# Camera_LED_Display.net
KiCad netlist of a schematic drawn in Altium Designer
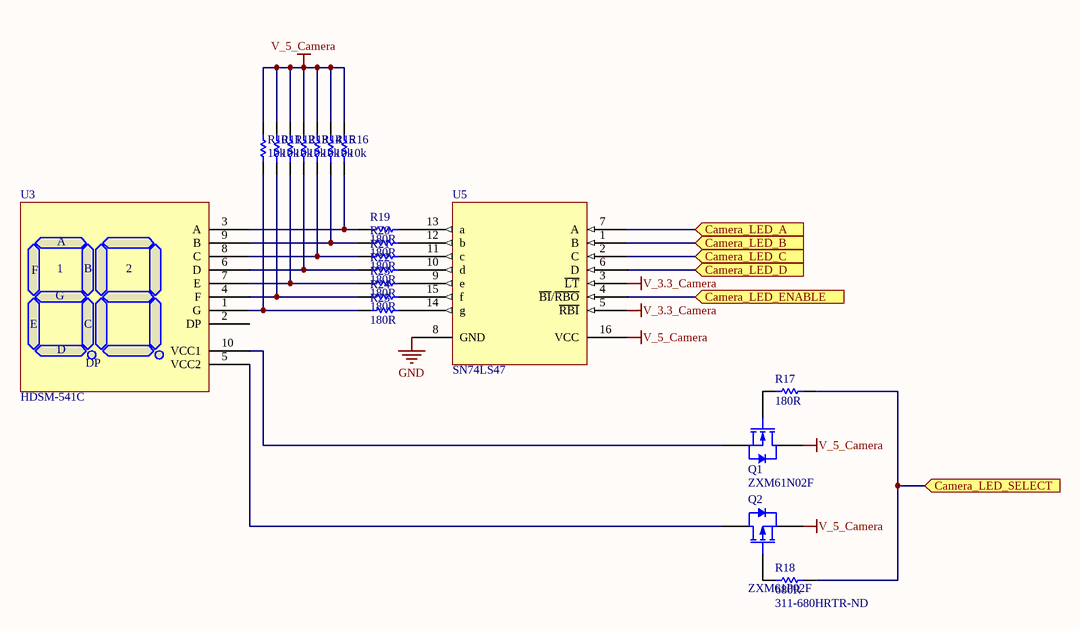
[diagram p0: Camera_LED_Display.SchDoc]

(export (version "E")
  (design (tool "Eeschema 10.0.6"))
  (components
    (comp (ref "Q1")
      (value "ZXM61N02F")
      (footprint "SOT-23")
      (description "20V N-channel enhancement mode MOSFET")
      (fields (field (name "MANUFACTURER") "Zetex") (field (name "PART NUMBER") "TF_ZXM61N02F"))
      (libsource (lib "ENEL429_4") (part "TF_ZXM61N02F"))
    )
    (comp (ref "Q2")
      (value "ZXM61P02F")
      (footprint "SOT23")
      (description "20V P-channel enhancement mode MOSFET")
      (fields (field (name "MANUFACTURER") "Zetex") (field (name "PART NUMBER") "TF_ZXM61P02F"))
      (libsource (lib "ENEL429_4") (part "TF_ZXM61P02F"))
    )
    (comp (ref "R10")
      (value "10k")
      (footprint "0603")
      (description "RES 10.0K OHM 1/10W 1% 0603 SMD")
      (fields (field (name "MANUFACTURER") "Yageo") (field (name "PART NUMBER") "RS_10k 0603"))
      (libsource (lib "ENEL429_4") (part "RS_10k 0603"))
    )
    (comp (ref "R11")
      (value "10k")
      (footprint "0603")
      (description "RES 10.0K OHM 1/10W 1% 0603 SMD")
      (fields (field (name "MANUFACTURER") "Yageo") (field (name "PART NUMBER") "RS_10k 0603"))
      (libsource (lib "ENEL429_4") (part "RS_10k 0603"))
    )
    (comp (ref "R12")
      (value "10k")
      (footprint "0603")
      (description "RES 10.0K OHM 1/10W 1% 0603 SMD")
      (fields (field (name "MANUFACTURER") "Yageo") (field (name "PART NUMBER") "RS_10k 0603"))
      (libsource (lib "ENEL429_4") (part "RS_10k 0603"))
    )
    (comp (ref "R13")
      (value "10k")
      (footprint "0603")
      (description "RES 10.0K OHM 1/10W 1% 0603 SMD")
      (fields (field (name "MANUFACTURER") "Yageo") (field (name "PART NUMBER") "RS_10k 0603"))
      (libsource (lib "ENEL429_4") (part "RS_10k 0603"))
    )
    (comp (ref "R14")
      (value "10k")
      (footprint "0603")
      (description "RES 10.0K OHM 1/10W 1% 0603 SMD")
      (fields (field (name "MANUFACTURER") "Yageo") (field (name "PART NUMBER") "RS_10k 0603"))
      (libsource (lib "ENEL429_4") (part "RS_10k 0603"))
    )
    (comp (ref "R15")
      (value "10k")
      (footprint "0603")
      (description "RES 10.0K OHM 1/10W 1% 0603 SMD")
      (fields (field (name "MANUFACTURER") "Yageo") (field (name "PART NUMBER") "RS_10k 0603"))
      (libsource (lib "ENEL429_4") (part "RS_10k 0603"))
    )
    (comp (ref "R16")
      (value "10k")
      (footprint "0603")
      (description "RES 10.0K OHM 1/10W 1% 0603 SMD")
      (fields (field (name "MANUFACTURER") "Yageo") (field (name "PART NUMBER") "RS_10k 0603"))
      (libsource (lib "ENEL429_4") (part "RS_10k 0603"))
    )
    (comp (ref "R17")
      (value "180R")
      (footprint "0603")
      (description "RES 180OHM 1/10W 1% 0603 SMD")
      (fields (field (name "MANUFACTURER") "Panasonic - ECG") (field (name "PART NUMBER") "RS_180R 0603"))
      (libsource (lib "ENEL429_4") (part "RS_180R 0603"))
    )
    (comp (ref "R18")
      (value "680R")
      (footprint "0603")
      (description "RES 680 OHM 1/10W 1% 0603 SMD")
      (fields
        (field (name "MANUFACTURER") "Yageo")
        (field (name "SUPPLIER PART NUMBER 1") "311-680HRTR-ND")
        (field (name "PART NUMBER") "RS_680R 0603")
      )
      (libsource (lib "ENEL429_4") (part "RS_680R 0603"))
    )
    (comp (ref "R19")
      (value "180R")
      (footprint "0603")
      (description "RES 180OHM 1/10W 1% 0603 SMD")
      (fields (field (name "MANUFACTURER") "Panasonic - ECG") (field (name "PART NUMBER") "RS_180R 0603"))
      (libsource (lib "ENEL429_4") (part "RS_180R 0603"))
    )
    (comp (ref "R20")
      (value "180R")
      (footprint "0603")
      (description "RES 180OHM 1/10W 1% 0603 SMD")
      (fields (field (name "MANUFACTURER") "Panasonic - ECG") (field (name "PART NUMBER") "RS_180R 0603"))
      (libsource (lib "ENEL429_4") (part "RS_180R 0603"))
    )
    (comp (ref "R21")
      (value "180R")
      (footprint "0603")
      (description "RES 180OHM 1/10W 1% 0603 SMD")
      (fields (field (name "MANUFACTURER") "Panasonic - ECG") (field (name "PART NUMBER") "RS_180R 0603"))
      (libsource (lib "ENEL429_4") (part "RS_180R 0603"))
    )
    (comp (ref "R22")
      (value "180R")
      (footprint "0603")
      (description "RES 180OHM 1/10W 1% 0603 SMD")
      (fields (field (name "MANUFACTURER") "Panasonic - ECG") (field (name "PART NUMBER") "RS_180R 0603"))
      (libsource (lib "ENEL429_4") (part "RS_180R 0603"))
    )
    (comp (ref "R23")
      (value "180R")
      (footprint "0603")
      (description "RES 180OHM 1/10W 1% 0603 SMD")
      (fields (field (name "MANUFACTURER") "Panasonic - ECG") (field (name "PART NUMBER") "RS_180R 0603"))
      (libsource (lib "ENEL429_4") (part "RS_180R 0603"))
    )
    (comp (ref "R24")
      (value "180R")
      (footprint "0603")
      (description "RES 180OHM 1/10W 1% 0603 SMD")
      (fields (field (name "MANUFACTURER") "Panasonic - ECG") (field (name "PART NUMBER") "RS_180R 0603"))
      (libsource (lib "ENEL429_4") (part "RS_180R 0603"))
    )
    (comp (ref "R25")
      (value "180R")
      (footprint "0603")
      (description "RES 180OHM 1/10W 1% 0603 SMD")
      (fields (field (name "MANUFACTURER") "Panasonic - ECG") (field (name "PART NUMBER") "RS_180R 0603"))
      (libsource (lib "ENEL429_4") (part "RS_180R 0603"))
    )
    (comp (ref "U3")
      (value "HDSM-541C")
      (footprint "HDSM-541C")
      (description "2 character 7 segment display")
      (fields (field (name "MANUFACTURER") "AVAGO TECHNOLOGIES"))
      (libsource (lib "Wacky_1") (part "HDSM-541C"))
    )
    (comp (ref "U5")
      (value "SN74LS47")
      (footprint "SOP127P780X200-16N")
      (fields (field (name "MANUFACTURER") "Texas Instruments"))
      (libsource (lib "Wacky_1") (part "SN74LS47"))
    )
  )
  (nets
    (net (code "1") (name "/Camera_LED_A") (class "Default")
      (node (ref "U5") (pin "7") (pinfunction "A_7") (pintype "input"))
    )
    (net (code "2") (name "/Camera_LED_B") (class "Default")
      (node (ref "U5") (pin "1") (pinfunction "B_1") (pintype "input"))
    )
    (net (code "3") (name "/Camera_LED_C") (class "Default")
      (node (ref "U5") (pin "2") (pinfunction "C_2") (pintype "input"))
    )
    (net (code "4") (name "/Camera_LED_D") (class "Default")
      (node (ref "U5") (pin "6") (pinfunction "D_6") (pintype "input"))
    )
    (net (code "5") (name "/Camera_LED_ENABLE") (class "Default")
      (node (ref "U5") (pin "4") (pinfunction "~{BI}/~{RBO}_4") (pintype "input"))
    )
    (net (code "6") (name "/Camera_LED_SELECT") (class "Default")
      (node (ref "R17") (pin "2") (pinfunction "2_2") (pintype "passive"))
      (node (ref "R18") (pin "2") (pinfunction "2_2") (pintype "passive"))
    )
    (net (code "7") (name "GND") (class "Default")
      (node (ref "U5") (pin "8") (pinfunction "GND_8") (pintype "passive"))
    )
    (net (code "8") (name "Net-(Q1-G)") (class "Default")
      (node (ref "Q1") (pin "1") (pinfunction "G_1") (pintype "passive"))
      (node (ref "R17") (pin "1") (pinfunction "1_1") (pintype "passive"))
    )
    (net (code "9") (name "Net-(Q1-S)") (class "Default")
      (node (ref "Q1") (pin "2") (pinfunction "S_2") (pintype "passive"))
      (node (ref "U3") (pin "10") (pinfunction "VCC1_10") (pintype "passive"))
    )
    (net (code "10") (name "Net-(Q2-D)") (class "Default")
      (node (ref "Q2") (pin "3") (pinfunction "D_3") (pintype "passive"))
      (node (ref "U3") (pin "5") (pinfunction "VCC2_5") (pintype "passive"))
    )
    (net (code "11") (name "Net-(Q2-G)") (class "Default")
      (node (ref "Q2") (pin "1") (pinfunction "G_1") (pintype "passive"))
      (node (ref "R18") (pin "1") (pinfunction "1_1") (pintype "passive"))
    )
    (net (code "12") (name "Net-(U3-A)") (class "Default")
      (node (ref "R16") (pin "1") (pinfunction "1_1") (pintype "passive"))
      (node (ref "R19") (pin "1") (pinfunction "1_1") (pintype "passive"))
      (node (ref "U3") (pin "3") (pinfunction "A_3") (pintype "passive"))
    )
    (net (code "13") (name "Net-(U3-B)") (class "Default")
      (node (ref "R15") (pin "1") (pinfunction "1_1") (pintype "passive"))
      (node (ref "R20") (pin "1") (pinfunction "1_1") (pintype "passive"))
      (node (ref "U3") (pin "9") (pinfunction "B_9") (pintype "passive"))
    )
    (net (code "14") (name "Net-(U3-C)") (class "Default")
      (node (ref "R14") (pin "1") (pinfunction "1_1") (pintype "passive"))
      (node (ref "R21") (pin "1") (pinfunction "1_1") (pintype "passive"))
      (node (ref "U3") (pin "8") (pinfunction "C_8") (pintype "passive"))
    )
    (net (code "15") (name "Net-(U3-D)") (class "Default")
      (node (ref "R13") (pin "1") (pinfunction "1_1") (pintype "passive"))
      (node (ref "R22") (pin "1") (pinfunction "1_1") (pintype "passive"))
      (node (ref "U3") (pin "6") (pinfunction "D_6") (pintype "passive"))
    )
    (net (code "16") (name "Net-(U3-E)") (class "Default")
      (node (ref "R12") (pin "1") (pinfunction "1_1") (pintype "passive"))
      (node (ref "R23") (pin "1") (pinfunction "1_1") (pintype "passive"))
      (node (ref "U3") (pin "7") (pinfunction "E_7") (pintype "passive"))
    )
    (net (code "17") (name "Net-(U3-F)") (class "Default")
      (node (ref "R11") (pin "1") (pinfunction "1_1") (pintype "passive"))
      (node (ref "R24") (pin "1") (pinfunction "1_1") (pintype "passive"))
      (node (ref "U3") (pin "4") (pinfunction "F_4") (pintype "passive"))
    )
    (net (code "18") (name "Net-(U3-G)") (class "Default")
      (node (ref "R10") (pin "1") (pinfunction "1_1") (pintype "passive"))
      (node (ref "R25") (pin "1") (pinfunction "1_1") (pintype "passive"))
      (node (ref "U3") (pin "1") (pinfunction "G_1") (pintype "passive"))
    )
    (net (code "19") (name "Net-(U5-a)") (class "Default")
      (node (ref "R19") (pin "2") (pinfunction "2_2") (pintype "passive"))
      (node (ref "U5") (pin "13") (pinfunction "a_13") (pintype "output"))
    )
    (net (code "20") (name "Net-(U5-b)") (class "Default")
      (node (ref "R20") (pin "2") (pinfunction "2_2") (pintype "passive"))
      (node (ref "U5") (pin "12") (pinfunction "b_12") (pintype "output"))
    )
    (net (code "21") (name "Net-(U5-c)") (class "Default")
      (node (ref "R21") (pin "2") (pinfunction "2_2") (pintype "passive"))
      (node (ref "U5") (pin "11") (pinfunction "c_11") (pintype "output"))
    )
    (net (code "22") (name "Net-(U5-d)") (class "Default")
      (node (ref "R22") (pin "2") (pinfunction "2_2") (pintype "passive"))
      (node (ref "U5") (pin "10") (pinfunction "d_10") (pintype "output"))
    )
    (net (code "23") (name "Net-(U5-e)") (class "Default")
      (node (ref "R23") (pin "2") (pinfunction "2_2") (pintype "passive"))
      (node (ref "U5") (pin "9") (pinfunction "e_9") (pintype "output"))
    )
    (net (code "24") (name "Net-(U5-f)") (class "Default")
      (node (ref "R24") (pin "2") (pinfunction "2_2") (pintype "passive"))
      (node (ref "U5") (pin "15") (pinfunction "f_15") (pintype "output"))
    )
    (net (code "25") (name "Net-(U5-g)") (class "Default")
      (node (ref "R25") (pin "2") (pinfunction "2_2") (pintype "passive"))
      (node (ref "U5") (pin "14") (pinfunction "g_14") (pintype "output"))
    )
    (net (code "26") (name "V_3.3_Camera") (class "Default")
      (node (ref "U5") (pin "3") (pinfunction "~{LT}_3") (pintype "input"))
      (node (ref "U5") (pin "5") (pinfunction "~{RBI}_5") (pintype "input"))
    )
    (net (code "27") (name "V_5_Camera") (class "Default")
      (node (ref "Q1") (pin "3") (pinfunction "D_3") (pintype "passive"))
      (node (ref "Q2") (pin "2") (pinfunction "S_2") (pintype "passive"))
      (node (ref "R10") (pin "2") (pinfunction "2_2") (pintype "passive"))
      (node (ref "R11") (pin "2") (pinfunction "2_2") (pintype "passive"))
      (node (ref "R12") (pin "2") (pinfunction "2_2") (pintype "passive"))
      (node (ref "R13") (pin "2") (pinfunction "2_2") (pintype "passive"))
      (node (ref "R14") (pin "2") (pinfunction "2_2") (pintype "passive"))
      (node (ref "R15") (pin "2") (pinfunction "2_2") (pintype "passive"))
      (node (ref "R16") (pin "2") (pinfunction "2_2") (pintype "passive"))
      (node (ref "U5") (pin "16") (pinfunction "VCC_16") (pintype "power_in"))
    )
    (net (code "28") (name "unconnected-(U3-DP-Pad2)") (class "Default")
      (node (ref "U3") (pin "2") (pinfunction "DP_2") (pintype "passive"))
    )
  )
)
